# INPUTS_OUTPUTS.net
KiCad netlist of a schematic drawn in Altium Designer
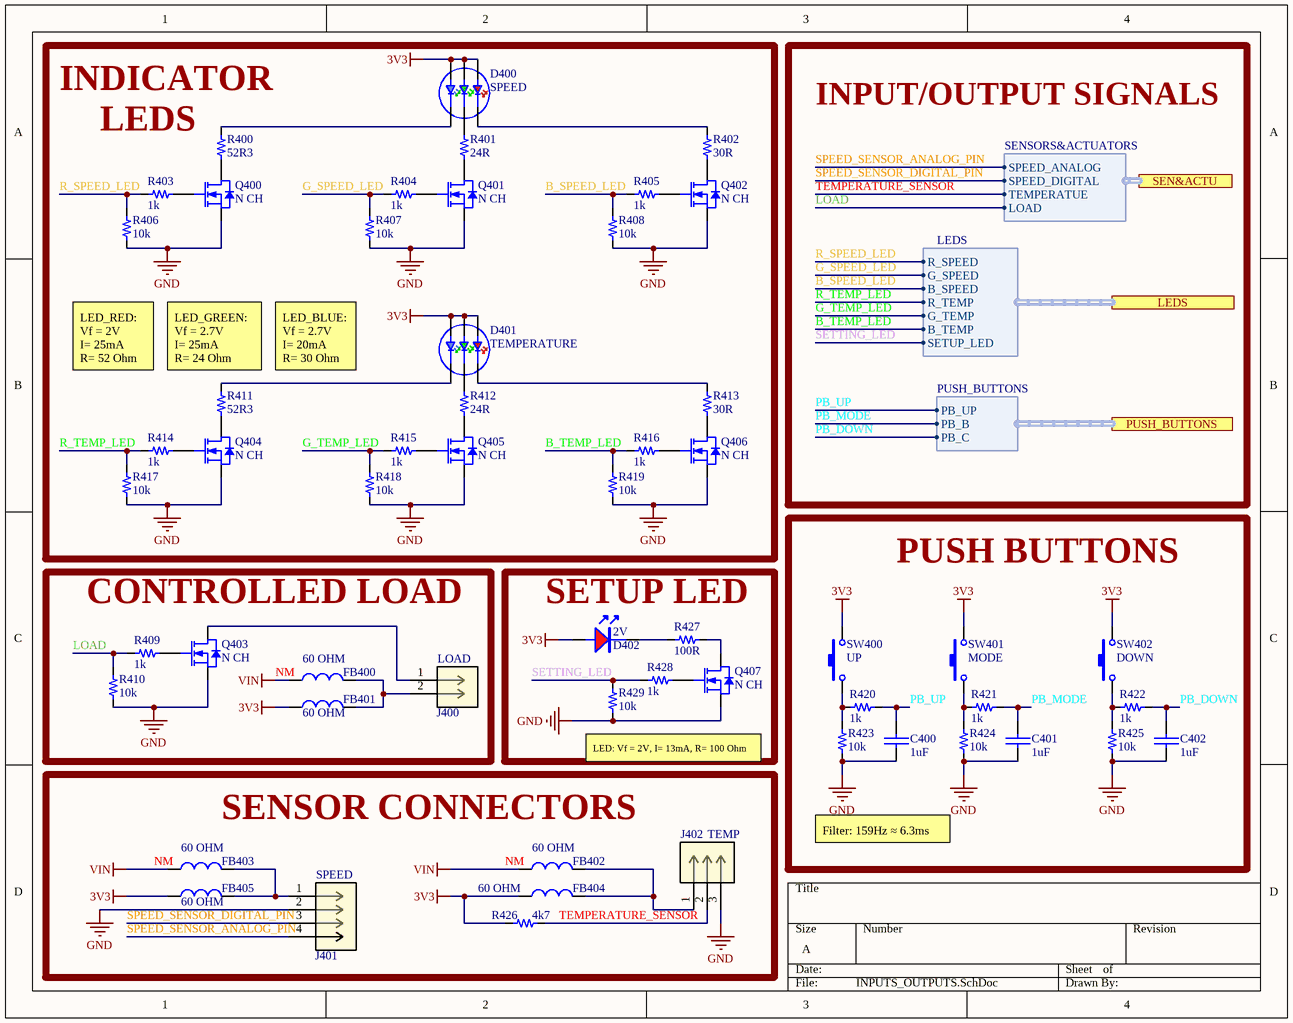
[diagram p0: INPUTS_OUTPUTS.SchDoc]

(export (version "E")
  (design (tool "Eeschema 10.0.6"))
  (components
    (comp (ref "C400")
      (value "1uF")
      (footprint "0603_cap")
      (description "50V 1uF X5R ±10% 0603 Multilayer Ceramic Capacitors MLCC - SMD/SMT ROHS")
      (fields
        (field (name "MANUFACTURER") "Samsung Electro-Mechanics")
        (field (name "MANUFACTURER PART NUMBER") "CL10A105KB8NNNC")
      )
      (libsource (lib "shared_lib") (part "Cap_1uF_0603_50V"))
    )
    (comp (ref "C401")
      (value "1uF")
      (footprint "0603_cap")
      (description "50V 1uF X5R ±10% 0603 Multilayer Ceramic Capacitors MLCC - SMD/SMT ROHS")
      (fields
        (field (name "MANUFACTURER") "Samsung Electro-Mechanics")
        (field (name "MANUFACTURER PART NUMBER") "CL10A105KB8NNNC")
      )
      (libsource (lib "shared_lib") (part "Cap_1uF_0603_50V"))
    )
    (comp (ref "C402")
      (value "1uF")
      (footprint "0603_cap")
      (description "50V 1uF X5R ±10% 0603 Multilayer Ceramic Capacitors MLCC - SMD/SMT ROHS")
      (fields
        (field (name "MANUFACTURER") "Samsung Electro-Mechanics")
        (field (name "MANUFACTURER PART NUMBER") "CL10A105KB8NNNC")
      )
      (libsource (lib "shared_lib") (part "Cap_1uF_0603_50V"))
    )
    (comp (ref "D400")
      (value "SPEED")
      (footprint "RGB_NS_3.5X3.7")
      (description "-30℃~+85℃ RGB 110° 3535(mm) Light Emitting Diodes (LED) ROHS")
      (fields
        (field (name "MANUFACTURER") "Foshan NationStar Optoelectronics")
        (field (name "MANUFACTURER PART NUMBER") "RS-3535MWAM")
      )
      (libsource (lib "shared_lib") (part "LED_RGB_3535_SMD"))
    )
    (comp (ref "D401")
      (value "TEMPERATURE")
      (footprint "RGB_NS_3.5X3.7")
      (description "-30℃~+85℃ RGB 110° 3535(mm) Light Emitting Diodes (LED) ROHS")
      (fields
        (field (name "MANUFACTURER") "Foshan NationStar Optoelectronics")
        (field (name "MANUFACTURER PART NUMBER") "RS-3535MWAM")
      )
      (libsource (lib "shared_lib") (part "LED_RGB_3535_SMD"))
    )
    (comp (ref "D402")
      (value "2V")
      (footprint "0805_LED")
      (description "LED RED CLEAR 0805 SMD")
      (fields
        (field (name "MANUFACTURER") "XINGLIGHT")
        (field (name "MANUFACTURER PART NUMBER") "XL-2012SURC")
      )
      (libsource (lib "shared_lib") (part "LED_0805_RED"))
    )
    (comp (ref "FB400")
      (value "60 OHM")
      (footprint "0603_fb")
      (description "2A 1 100mΩ 60Ω@100MHz ±25% 0603 Ferrite Beads ROHS")
      (fields
        (field (name "MANUFACTURER") "TAI-TECH")
        (field (name "MANUFACTURER PART NUMBER") "HCB1608KF-600T20")
        (field (name "USAGE") "NM")
      )
      (libsource (lib "shared_lib") (part "FB_60_0603_2A"))
    )
    (comp (ref "FB401")
      (value "60 OHM")
      (footprint "0603_fb")
      (description "2A 1 100mΩ 60Ω@100MHz ±25% 0603 Ferrite Beads ROHS")
      (fields
        (field (name "MANUFACTURER") "TAI-TECH")
        (field (name "MANUFACTURER PART NUMBER") "HCB1608KF-600T20")
      )
      (libsource (lib "shared_lib") (part "FB_60_0603_2A"))
    )
    (comp (ref "FB402")
      (value "60 OHM")
      (footprint "0603_fb")
      (description "2A 1 100mΩ 60Ω@100MHz ±25% 0603 Ferrite Beads ROHS")
      (fields
        (field (name "MANUFACTURER") "TAI-TECH")
        (field (name "MANUFACTURER PART NUMBER") "HCB1608KF-600T20")
        (field (name "USAGE") "NM")
      )
      (libsource (lib "shared_lib") (part "FB_60_0603_2A"))
    )
    (comp (ref "FB403")
      (value "60 OHM")
      (footprint "0603_fb")
      (description "2A 1 100mΩ 60Ω@100MHz ±25% 0603 Ferrite Beads ROHS")
      (fields
        (field (name "MANUFACTURER") "TAI-TECH")
        (field (name "MANUFACTURER PART NUMBER") "HCB1608KF-600T20")
        (field (name "USAGE") "NM")
      )
      (libsource (lib "shared_lib") (part "FB_60_0603_2A"))
    )
    (comp (ref "FB404")
      (value "60 OHM")
      (footprint "0603_fb")
      (description "2A 1 100mΩ 60Ω@100MHz ±25% 0603 Ferrite Beads ROHS")
      (fields
        (field (name "MANUFACTURER") "TAI-TECH")
        (field (name "MANUFACTURER PART NUMBER") "HCB1608KF-600T20")
      )
      (libsource (lib "shared_lib") (part "FB_60_0603_2A"))
    )
    (comp (ref "FB405")
      (value "60 OHM")
      (footprint "0603_fb")
      (description "2A 1 100mΩ 60Ω@100MHz ±25% 0603 Ferrite Beads ROHS")
      (fields
        (field (name "MANUFACTURER") "TAI-TECH")
        (field (name "MANUFACTURER PART NUMBER") "HCB1608KF-600T20")
      )
      (libsource (lib "shared_lib") (part "FB_60_0603_2A"))
    )
    (comp (ref "J400")
      (value "LOAD")
      (footprint "CON_2X1_TH_2.54MM")
      (description "CONN HEADER VERT 2POS 2.54MM")
      (fields
        (field (name "MANUFACTURER") "Amphenol ICC (FCI)")
        (field (name "MANUFACTURER PART NUMBER") "10129378-902001BLF")
      )
      (libsource (lib "Bicycle_project") (part "Con_2x1_TH_2.54mm"))
    )
    (comp (ref "J401")
      (value "SPEED")
      (footprint "CON_4X1_TH_2.54MM")
      (description "CONN HEADER VERT 4POS 2.54MM")
      (fields
        (field (name "MANUFACTURER") "Amphenol ICC (FCI)")
        (field (name "MANUFACTURER PART NUMBER") "10129378-904001BLF")
      )
      (libsource (lib "Bicycle_project") (part "Con_4X1_TH_2.54mm"))
    )
    (comp (ref "J402")
      (value "TEMP")
      (footprint "CON_3X1_TH_2.54MM")
      (description "CONN HEADER VERT 3POS 2.54MM")
      (fields
        (field (name "MANUFACTURER") "Amphenol ICC (FCI)")
        (field (name "MANUFACTURER PART NUMBER") "10129378-903001BLF")
      )
      (libsource (lib "Bicycle_project") (part "Con_3X1_TH_2.54mm"))
    )
    (comp (ref "Q400")
      (value "N CH")
      (footprint "SOT_23_3")
      (description "MOSFET N-CH 20V SOT23")
      (fields (field (name "MANUFACTURER") "Doeshare") (field (name "MANUFACTURER PART NUMBER") "DN2302S"))
      (libsource (lib "shared_lib") (part "Q_NFET_20V_3.2A_SOT23"))
    )
    (comp (ref "Q401")
      (value "N CH")
      (footprint "SOT_23_3")
      (description "MOSFET N-CH 20V SOT23")
      (fields (field (name "MANUFACTURER") "Doeshare") (field (name "MANUFACTURER PART NUMBER") "DN2302S"))
      (libsource (lib "shared_lib") (part "Q_NFET_20V_3.2A_SOT23"))
    )
    (comp (ref "Q402")
      (value "N CH")
      (footprint "SOT_23_3")
      (description "MOSFET N-CH 20V SOT23")
      (fields (field (name "MANUFACTURER") "Doeshare") (field (name "MANUFACTURER PART NUMBER") "DN2302S"))
      (libsource (lib "shared_lib") (part "Q_NFET_20V_3.2A_SOT23"))
    )
    (comp (ref "Q403")
      (value "N CH")
      (footprint "SOT_23_3")
      (description "MOSFET N-CH 20V SOT23")
      (fields (field (name "MANUFACTURER") "Doeshare") (field (name "MANUFACTURER PART NUMBER") "DN2302S"))
      (libsource (lib "shared_lib") (part "Q_NFET_20V_3.2A_SOT23"))
    )
    (comp (ref "Q404")
      (value "N CH")
      (footprint "SOT_23_3")
      (description "MOSFET N-CH 20V SOT23")
      (fields (field (name "MANUFACTURER") "Doeshare") (field (name "MANUFACTURER PART NUMBER") "DN2302S"))
      (libsource (lib "shared_lib") (part "Q_NFET_20V_3.2A_SOT23"))
    )
    (comp (ref "Q405")
      (value "N CH")
      (footprint "SOT_23_3")
      (description "MOSFET N-CH 20V SOT23")
      (fields (field (name "MANUFACTURER") "Doeshare") (field (name "MANUFACTURER PART NUMBER") "DN2302S"))
      (libsource (lib "shared_lib") (part "Q_NFET_20V_3.2A_SOT23"))
    )
    (comp (ref "Q406")
      (value "N CH")
      (footprint "SOT_23_3")
      (description "MOSFET N-CH 20V SOT23")
      (fields (field (name "MANUFACTURER") "Doeshare") (field (name "MANUFACTURER PART NUMBER") "DN2302S"))
      (libsource (lib "shared_lib") (part "Q_NFET_20V_3.2A_SOT23"))
    )
    (comp (ref "Q407")
      (value "N CH")
      (footprint "SOT_23_3")
      (description "MOSFET N-CH 20V SOT23")
      (fields (field (name "MANUFACTURER") "Doeshare") (field (name "MANUFACTURER PART NUMBER") "DN2302S"))
      (libsource (lib "shared_lib") (part "Q_NFET_20V_3.2A_SOT23"))
    )
    (comp (ref "R400")
      (value "52R3")
      (footprint "0603_res")
      (description "RES SMD 52R3 OHM 1% 1/10W 0603")
      (fields
        (field (name "MANUFACTURER") "FOJAN")
        (field (name "MANUFACTURER PART NUMBER") "FRC0603F52R3TS")
      )
      (libsource (lib "shared_lib") (part "Res_52R3_0603_1/10W_1"))
    )
    (comp (ref "R401")
      (value "24R")
      (footprint "0603_res")
      (description "RES SMD 24R OHM 5% 1/10W 0603")
      (fields
        (field (name "MANUFACTURER") "FOJAN")
        (field (name "MANUFACTURER PART NUMBER") "FRC0603J240 TS")
      )
      (libsource (lib "shared_lib") (part "Res_24R_0603_1/10W"))
    )
    (comp (ref "R402")
      (value "30R")
      (footprint "0603_res")
      (description "RES SMD 30R OHM 1% 1/10W 0603")
      (fields
        (field (name "MANUFACTURER") "FOJAN")
        (field (name "MANUFACTURER PART NUMBER") "FRC0603F30R0TS")
      )
      (libsource (lib "shared_lib") (part "Res_30R_0603_1/10W"))
    )
    (comp (ref "R403")
      (value "1k")
      (footprint "0603_res")
      (description "RES SMD 1k OHM 5% 1/10W 0603")
      (fields
        (field (name "MANUFACTURER") "FOJAN")
        (field (name "MANUFACTURER PART NUMBER") "FRC0603J102 TS")
      )
      (libsource (lib "shared_lib") (part "Res_1k_0603_1/10W"))
    )
    (comp (ref "R404")
      (value "1k")
      (footprint "0603_res")
      (description "RES SMD 1k OHM 5% 1/10W 0603")
      (fields
        (field (name "MANUFACTURER") "FOJAN")
        (field (name "MANUFACTURER PART NUMBER") "FRC0603J102 TS")
      )
      (libsource (lib "shared_lib") (part "Res_1k_0603_1/10W"))
    )
    (comp (ref "R405")
      (value "1k")
      (footprint "0603_res")
      (description "RES SMD 1k OHM 5% 1/10W 0603")
      (fields
        (field (name "MANUFACTURER") "FOJAN")
        (field (name "MANUFACTURER PART NUMBER") "FRC0603J102 TS")
      )
      (libsource (lib "shared_lib") (part "Res_1k_0603_1/10W"))
    )
    (comp (ref "R406")
      (value "10k")
      (footprint "0603_res")
      (description "RES SMD 10k OHM 5% 1/10W 0603")
      (fields (field (name "MANUFACTURER") "FOJAN") (field (name "MANUFACTURER PART NUMBER") "FRC0603J103TS"))
      (libsource (lib "shared_lib") (part "Res_10k_0603_1/10W"))
    )
    (comp (ref "R407")
      (value "10k")
      (footprint "0603_res")
      (description "RES SMD 10k OHM 5% 1/10W 0603")
      (fields (field (name "MANUFACTURER") "FOJAN") (field (name "MANUFACTURER PART NUMBER") "FRC0603J103TS"))
      (libsource (lib "shared_lib") (part "Res_10k_0603_1/10W"))
    )
    (comp (ref "R408")
      (value "10k")
      (footprint "0603_res")
      (description "RES SMD 10k OHM 5% 1/10W 0603")
      (fields (field (name "MANUFACTURER") "FOJAN") (field (name "MANUFACTURER PART NUMBER") "FRC0603J103TS"))
      (libsource (lib "shared_lib") (part "Res_10k_0603_1/10W"))
    )
    (comp (ref "R409")
      (value "1k")
      (footprint "0603_res")
      (description "RES SMD 1k OHM 5% 1/10W 0603")
      (fields
        (field (name "MANUFACTURER") "FOJAN")
        (field (name "MANUFACTURER PART NUMBER") "FRC0603J102 TS")
      )
      (libsource (lib "shared_lib") (part "Res_1k_0603_1/10W"))
    )
    (comp (ref "R410")
      (value "10k")
      (footprint "0603_res")
      (description "RES SMD 10k OHM 5% 1/10W 0603")
      (fields (field (name "MANUFACTURER") "FOJAN") (field (name "MANUFACTURER PART NUMBER") "FRC0603J103TS"))
      (libsource (lib "shared_lib") (part "Res_10k_0603_1/10W"))
    )
    (comp (ref "R411")
      (value "52R3")
      (footprint "0603_res")
      (description "RES SMD 52R3 OHM 1% 1/10W 0603")
      (fields
        (field (name "MANUFACTURER") "FOJAN")
        (field (name "MANUFACTURER PART NUMBER") "FRC0603F52R3TS")
      )
      (libsource (lib "shared_lib") (part "Res_52R3_0603_1/10W_1"))
    )
    (comp (ref "R412")
      (value "24R")
      (footprint "0603_res")
      (description "RES SMD 24R OHM 5% 1/10W 0603")
      (fields
        (field (name "MANUFACTURER") "FOJAN")
        (field (name "MANUFACTURER PART NUMBER") "FRC0603J240 TS")
      )
      (libsource (lib "shared_lib") (part "Res_24R_0603_1/10W"))
    )
    (comp (ref "R413")
      (value "30R")
      (footprint "0603_res")
      (description "RES SMD 30R OHM 1% 1/10W 0603")
      (fields
        (field (name "MANUFACTURER") "FOJAN")
        (field (name "MANUFACTURER PART NUMBER") "FRC0603F30R0TS")
      )
      (libsource (lib "shared_lib") (part "Res_30R_0603_1/10W"))
    )
    (comp (ref "R414")
      (value "1k")
      (footprint "0603_res")
      (description "RES SMD 1k OHM 5% 1/10W 0603")
      (fields
        (field (name "MANUFACTURER") "FOJAN")
        (field (name "MANUFACTURER PART NUMBER") "FRC0603J102 TS")
      )
      (libsource (lib "shared_lib") (part "Res_1k_0603_1/10W"))
    )
    (comp (ref "R415")
      (value "1k")
      (footprint "0603_res")
      (description "RES SMD 1k OHM 5% 1/10W 0603")
      (fields
        (field (name "MANUFACTURER") "FOJAN")
        (field (name "MANUFACTURER PART NUMBER") "FRC0603J102 TS")
      )
      (libsource (lib "shared_lib") (part "Res_1k_0603_1/10W"))
    )
    (comp (ref "R416")
      (value "1k")
      (footprint "0603_res")
      (description "RES SMD 1k OHM 5% 1/10W 0603")
      (fields
        (field (name "MANUFACTURER") "FOJAN")
        (field (name "MANUFACTURER PART NUMBER") "FRC0603J102 TS")
      )
      (libsource (lib "shared_lib") (part "Res_1k_0603_1/10W"))
    )
    (comp (ref "R417")
      (value "10k")
      (footprint "0603_res")
      (description "RES SMD 10k OHM 5% 1/10W 0603")
      (fields (field (name "MANUFACTURER") "FOJAN") (field (name "MANUFACTURER PART NUMBER") "FRC0603J103TS"))
      (libsource (lib "shared_lib") (part "Res_10k_0603_1/10W"))
    )
    (comp (ref "R418")
      (value "10k")
      (footprint "0603_res")
      (description "RES SMD 10k OHM 5% 1/10W 0603")
      (fields (field (name "MANUFACTURER") "FOJAN") (field (name "MANUFACTURER PART NUMBER") "FRC0603J103TS"))
      (libsource (lib "shared_lib") (part "Res_10k_0603_1/10W"))
    )
    (comp (ref "R419")
      (value "10k")
      (footprint "0603_res")
      (description "RES SMD 10k OHM 5% 1/10W 0603")
      (fields (field (name "MANUFACTURER") "FOJAN") (field (name "MANUFACTURER PART NUMBER") "FRC0603J103TS"))
      (libsource (lib "shared_lib") (part "Res_10k_0603_1/10W"))
    )
    (comp (ref "R420")
      (value "1k")
      (footprint "0603_res")
      (description "RES SMD 1k OHM 5% 1/10W 0603")
      (fields
        (field (name "MANUFACTURER") "FOJAN")
        (field (name "MANUFACTURER PART NUMBER") "FRC0603J102 TS")
      )
      (libsource (lib "shared_lib") (part "Res_1k_0603_1/10W"))
    )
    (comp (ref "R421")
      (value "1k")
      (footprint "0603_res")
      (description "RES SMD 1k OHM 5% 1/10W 0603")
      (fields
        (field (name "MANUFACTURER") "FOJAN")
        (field (name "MANUFACTURER PART NUMBER") "FRC0603J102 TS")
      )
      (libsource (lib "shared_lib") (part "Res_1k_0603_1/10W"))
    )
    (comp (ref "R422")
      (value "1k")
      (footprint "0603_res")
      (description "RES SMD 1k OHM 5% 1/10W 0603")
      (fields
        (field (name "MANUFACTURER") "FOJAN")
        (field (name "MANUFACTURER PART NUMBER") "FRC0603J102 TS")
      )
      (libsource (lib "shared_lib") (part "Res_1k_0603_1/10W"))
    )
    (comp (ref "R423")
      (value "10k")
      (footprint "0603_res")
      (description "RES SMD 10k OHM 5% 1/10W 0603")
      (fields (field (name "MANUFACTURER") "FOJAN") (field (name "MANUFACTURER PART NUMBER") "FRC0603J103TS"))
      (libsource (lib "shared_lib") (part "Res_10k_0603_1/10W"))
    )
    (comp (ref "R424")
      (value "10k")
      (footprint "0603_res")
      (description "RES SMD 10k OHM 5% 1/10W 0603")
      (fields (field (name "MANUFACTURER") "FOJAN") (field (name "MANUFACTURER PART NUMBER") "FRC0603J103TS"))
      (libsource (lib "shared_lib") (part "Res_10k_0603_1/10W"))
    )
    (comp (ref "R425")
      (value "10k")
      (footprint "0603_res")
      (description "RES SMD 10k OHM 5% 1/10W 0603")
      (fields (field (name "MANUFACTURER") "FOJAN") (field (name "MANUFACTURER PART NUMBER") "FRC0603J103TS"))
      (libsource (lib "shared_lib") (part "Res_10k_0603_1/10W"))
    )
    (comp (ref "R426")
      (value "4k7")
      (footprint "0603_res")
      (description "RES SMD 4k7 OHM 5% 1/10W 0603")
      (fields
        (field (name "MANUFACTURER") "FOJAN")
        (field (name "MANUFACTURER PART NUMBER") "FRC0603J472 TS")
      )
      (libsource (lib "shared_lib") (part "Res_4k7_0603_1/10W"))
    )
    (comp (ref "R427")
      (value "100R")
      (footprint "0603_res")
      (description "RES SMD 100R OHM 5% 1/10W 0603")
      (fields
        (field (name "MANUFACTURER") "FOJAN")
        (field (name "MANUFACTURER PART NUMBER") "FRC0603J101 TS")
      )
      (libsource (lib "shared_lib") (part "Res_100R_0603_1/10W"))
    )
    (comp (ref "R428")
      (value "1k")
      (footprint "0603_res")
      (description "RES SMD 1k OHM 5% 1/10W 0603")
      (fields
        (field (name "MANUFACTURER") "FOJAN")
        (field (name "MANUFACTURER PART NUMBER") "FRC0603J102 TS")
      )
      (libsource (lib "shared_lib") (part "Res_1k_0603_1/10W"))
    )
    (comp (ref "R429")
      (value "10k")
      (footprint "0603_res")
      (description "RES SMD 10k OHM 5% 1/10W 0603")
      (fields (field (name "MANUFACTURER") "FOJAN") (field (name "MANUFACTURER PART NUMBER") "FRC0603J103TS"))
      (libsource (lib "shared_lib") (part "Res_10k_0603_1/10W"))
    )
    (comp (ref "SW400")
      (value "UP")
      (footprint "Sw_PUSH_4.5x4.5x5mm")
      (description "SWITCH TACTILE SPST-NO 0.05A 12V")
      (fields
        (field (name "MANUFACTURER") "BZCN")
        (field (name "MANUFACTURER PART NUMBER") "TSC015A05026A")
        (field (name "LAST MODIFIED BY") "N-A.Potosi")
      )
      (libsource (lib "shared_lib") (part "Sw_PUSH_4.5x4.5x5.0xmm"))
    )
    (comp (ref "SW401")
      (value "MODE")
      (footprint "Sw_PUSH_4.5x4.5x5mm")
      (description "SWITCH TACTILE SPST-NO 0.05A 12V")
      (fields
        (field (name "MANUFACTURER") "BZCN")
        (field (name "MANUFACTURER PART NUMBER") "TSC015A05026A")
        (field (name "LAST MODIFIED BY") "N-A.Potosi")
      )
      (libsource (lib "shared_lib") (part "Sw_PUSH_4.5x4.5x5.0xmm"))
    )
    (comp (ref "SW402")
      (value "DOWN")
      (footprint "Sw_PUSH_4.5x4.5x5mm")
      (description "SWITCH TACTILE SPST-NO 0.05A 12V")
      (fields
        (field (name "MANUFACTURER") "BZCN")
        (field (name "MANUFACTURER PART NUMBER") "TSC015A05026A")
        (field (name "LAST MODIFIED BY") "N-A.Potosi")
      )
      (libsource (lib "shared_lib") (part "Sw_PUSH_4.5x4.5x5.0xmm"))
    )
  )
  (nets
    (net (code "4") (name "/B_SPEED_LED") (class "Default")
      (node (ref "R405") (pin "1") (pinfunction "1_1") (pintype "passive"))
      (node (ref "R408") (pin "2") (pinfunction "2_2") (pintype "passive"))
    )
    (net (code "5") (name "/B_TEMP_LED") (class "Default")
      (node (ref "R416") (pin "1") (pinfunction "1_1") (pintype "passive"))
      (node (ref "R419") (pin "2") (pinfunction "2_2") (pintype "passive"))
    )
    (net (code "6") (name "/G_SPEED_LED") (class "Default")
      (node (ref "R404") (pin "1") (pinfunction "1_1") (pintype "passive"))
      (node (ref "R407") (pin "2") (pinfunction "2_2") (pintype "passive"))
    )
    (net (code "7") (name "/G_TEMP_LED") (class "Default")
      (node (ref "R415") (pin "1") (pinfunction "1_1") (pintype "passive"))
      (node (ref "R418") (pin "2") (pinfunction "2_2") (pintype "passive"))
    )
    (net (code "8") (name "/LOAD") (class "Default")
      (node (ref "R409") (pin "1") (pinfunction "1_1") (pintype "passive"))
      (node (ref "R410") (pin "2") (pinfunction "2_2") (pintype "passive"))
    )
    (net (code "9") (name "/PB_DOWN") (class "Default")
      (node (ref "C402") (pin "2") (pinfunction "2_2") (pintype "passive"))
      (node (ref "R422") (pin "2") (pinfunction "2_2") (pintype "passive"))
    )
    (net (code "10") (name "/PB_MODE") (class "Default")
      (node (ref "C401") (pin "2") (pinfunction "2_2") (pintype "passive"))
      (node (ref "R421") (pin "2") (pinfunction "2_2") (pintype "passive"))
    )
    (net (code "11") (name "/PB_UP") (class "Default")
      (node (ref "C400") (pin "2") (pinfunction "2_2") (pintype "passive"))
      (node (ref "R420") (pin "2") (pinfunction "2_2") (pintype "passive"))
    )
    (net (code "12") (name "/R_SPEED_LED") (class "Default")
      (node (ref "R403") (pin "1") (pinfunction "1_1") (pintype "passive"))
      (node (ref "R406") (pin "2") (pinfunction "2_2") (pintype "passive"))
    )
    (net (code "13") (name "/R_TEMP_LED") (class "Default")
      (node (ref "R414") (pin "1") (pinfunction "1_1") (pintype "passive"))
      (node (ref "R417") (pin "2") (pinfunction "2_2") (pintype "passive"))
    )
    (net (code "14") (name "/SETTING_LED") (class "Default")
      (node (ref "R428") (pin "1") (pinfunction "1_1") (pintype "passive"))
      (node (ref "R429") (pin "2") (pinfunction "2_2") (pintype "passive"))
    )
    (net (code "15") (name "/SPEED_SENSOR_ANALOG_PIN") (class "Default")
      (node (ref "J401") (pin "4") (pinfunction "4_4") (pintype "passive"))
    )
    (net (code "16") (name "/SPEED_SENSOR_DIGITAL_PIN") (class "Default")
      (node (ref "J401") (pin "3") (pinfunction "3_3") (pintype "passive"))
    )
    (net (code "17") (name "/TEMPERATURE_SENSOR") (class "Default")
      (node (ref "J402") (pin "2") (pinfunction "2_2") (pintype "passive"))
      (node (ref "R426") (pin "2") (pinfunction "2_2") (pintype "passive"))
    )
    (net (code "21") (name "3V3") (class "Default")
      (node (ref "D400") (pin "4") (pinfunction "4_4") (pintype "passive"))
      (node (ref "D400") (pin "5") (pinfunction "5_5") (pintype "passive"))
      (node (ref "D400") (pin "6") (pinfunction "6_6") (pintype "passive"))
      (node (ref "D401") (pin "4") (pinfunction "4_4") (pintype "passive"))
      (node (ref "D401") (pin "5") (pinfunction "5_5") (pintype "passive"))
      (node (ref "D401") (pin "6") (pinfunction "6_6") (pintype "passive"))
      (node (ref "D402") (pin "1") (pinfunction "A_1") (pintype "passive"))
      (node (ref "FB401") (pin "1") (pinfunction "1_1") (pintype "passive"))
      (node (ref "FB404") (pin "1") (pinfunction "1_1") (pintype "passive"))
      (node (ref "FB405") (pin "1") (pinfunction "1_1") (pintype "passive"))
      (node (ref "R426") (pin "1") (pinfunction "1_1") (pintype "passive"))
      (node (ref "SW400") (pin "2") (pinfunction "2_2") (pintype "passive"))
      (node (ref "SW401") (pin "2") (pinfunction "2_2") (pintype "passive"))
      (node (ref "SW402") (pin "2") (pinfunction "2_2") (pintype "passive"))
    )
    (net (code "22") (name "GND") (class "Default")
      (node (ref "C400") (pin "1") (pinfunction "1_1") (pintype "passive"))
      (node (ref "C401") (pin "1") (pinfunction "1_1") (pintype "passive"))
      (node (ref "C402") (pin "1") (pinfunction "1_1") (pintype "passive"))
      (node (ref "J401") (pin "2") (pinfunction "2_2") (pintype "passive"))
      (node (ref "J402") (pin "3") (pinfunction "3_3") (pintype "passive"))
      (node (ref "Q400") (pin "2") (pinfunction "S_2") (pintype "passive"))
      (node (ref "Q401") (pin "2") (pinfunction "S_2") (pintype "passive"))
      (node (ref "Q402") (pin "2") (pinfunction "S_2") (pintype "passive"))
      (node (ref "Q403") (pin "2") (pinfunction "S_2") (pintype "passive"))
      (node (ref "Q404") (pin "2") (pinfunction "S_2") (pintype "passive"))
      (node (ref "Q405") (pin "2") (pinfunction "S_2") (pintype "passive"))
      (node (ref "Q406") (pin "2") (pinfunction "S_2") (pintype "passive"))
      (node (ref "Q407") (pin "2") (pinfunction "S_2") (pintype "passive"))
      (node (ref "R406") (pin "1") (pinfunction "1_1") (pintype "passive"))
      (node (ref "R407") (pin "1") (pinfunction "1_1") (pintype "passive"))
      (node (ref "R408") (pin "1") (pinfunction "1_1") (pintype "passive"))
      (node (ref "R410") (pin "1") (pinfunction "1_1") (pintype "passive"))
      (node (ref "R417") (pin "1") (pinfunction "1_1") (pintype "passive"))
      (node (ref "R418") (pin "1") (pinfunction "1_1") (pintype "passive"))
      (node (ref "R419") (pin "1") (pinfunction "1_1") (pintype "passive"))
      (node (ref "R423") (pin "1") (pinfunction "1_1") (pintype "passive"))
      (node (ref "R424") (pin "1") (pinfunction "1_1") (pintype "passive"))
      (node (ref "R425") (pin "1") (pinfunction "1_1") (pintype "passive"))
      (node (ref "R429") (pin "1") (pinfunction "1_1") (pintype "passive"))
    )
    (net (code "23") (name "Net-(D400-Pad1)") (class "Default")
      (node (ref "D400") (pin "1") (pinfunction "1_1") (pintype "passive"))
      (node (ref "R400") (pin "2") (pinfunction "2_2") (pintype "passive"))
    )
    (net (code "24") (name "Net-(D400-Pad2)") (class "Default")
      (node (ref "D400") (pin "2") (pinfunction "2_2") (pintype "passive"))
      (node (ref "R401") (pin "2") (pinfunction "2_2") (pintype "passive"))
    )
    (net (code "25") (name "Net-(D400-Pad3)") (class "Default")
      (node (ref "D400") (pin "3") (pinfunction "3_3") (pintype "passive"))
      (node (ref "R402") (pin "2") (pinfunction "2_2") (pintype "passive"))
    )
    (net (code "26") (name "Net-(D401-Pad1)") (class "Default")
      (node (ref "D401") (pin "1") (pinfunction "1_1") (pintype "passive"))
      (node (ref "R411") (pin "2") (pinfunction "2_2") (pintype "passive"))
    )
    (net (code "27") (name "Net-(D401-Pad2)") (class "Default")
      (node (ref "D401") (pin "2") (pinfunction "2_2") (pintype "passive"))
      (node (ref "R412") (pin "2") (pinfunction "2_2") (pintype "passive"))
    )
    (net (code "28") (name "Net-(D401-Pad3)") (class "Default")
      (node (ref "D401") (pin "3") (pinfunction "3_3") (pintype "passive"))
      (node (ref "R413") (pin "2") (pinfunction "2_2") (pintype "passive"))
    )
    (net (code "29") (name "Net-(D402-Pad2)") (class "Default")
      (node (ref "D402") (pin "2") (pinfunction "2_2") (pintype "passive"))
      (node (ref "R427") (pin "2") (pinfunction "2_2") (pintype "passive"))
    )
    (net (code "30") (name "Net-(FB400-Pad2)") (class "Default")
      (node (ref "FB400") (pin "2") (pinfunction "2_2") (pintype "passive"))
      (node (ref "FB401") (pin "2") (pinfunction "2_2") (pintype "passive"))
      (node (ref "J400") (pin "2") (pinfunction "2_2") (pintype "passive"))
    )
    (net (code "31") (name "Net-(FB402-Pad2)") (class "Default")
      (node (ref "FB402") (pin "2") (pinfunction "2_2") (pintype "passive"))
      (node (ref "FB404") (pin "2") (pinfunction "2_2") (pintype "passive"))
      (node (ref "J402") (pin "1") (pinfunction "1_1") (pintype "passive"))
    )
    (net (code "32") (name "Net-(FB403-Pad2)") (class "Default")
      (node (ref "FB403") (pin "2") (pinfunction "2_2") (pintype "passive"))
      (node (ref "FB405") (pin "2") (pinfunction "2_2") (pintype "passive"))
      (node (ref "J401") (pin "1") (pinfunction "1_1") (pintype "passive"))
    )
    (net (code "33") (name "Net-(Q400-D)") (class "Default")
      (node (ref "Q400") (pin "3") (pinfunction "D_3") (pintype "passive"))
      (node (ref "R400") (pin "1") (pinfunction "1_1") (pintype "passive"))
    )
    (net (code "34") (name "Net-(Q400-G)") (class "Default")
      (node (ref "Q400") (pin "1") (pinfunction "G_1") (pintype "passive"))
      (node (ref "R403") (pin "2") (pinfunction "2_2") (pintype "passive"))
    )
    (net (code "35") (name "Net-(Q401-D)") (class "Default")
      (node (ref "Q401") (pin "3") (pinfunction "D_3") (pintype "passive"))
      (node (ref "R401") (pin "1") (pinfunction "1_1") (pintype "passive"))
    )
    (net (code "36") (name "Net-(Q401-G)") (class "Default")
      (node (ref "Q401") (pin "1") (pinfunction "G_1") (pintype "passive"))
      (node (ref "R404") (pin "2") (pinfunction "2_2") (pintype "passive"))
    )
    (net (code "37") (name "Net-(Q402-D)") (class "Default")
      (node (ref "Q402") (pin "3") (pinfunction "D_3") (pintype "passive"))
      (node (ref "R402") (pin "1") (pinfunction "1_1") (pintype "passive"))
    )
    (net (code "38") (name "Net-(Q402-G)") (class "Default")
      (node (ref "Q402") (pin "1") (pinfunction "G_1") (pintype "passive"))
      (node (ref "R405") (pin "2") (pinfunction "2_2") (pintype "passive"))
    )
    (net (code "39") (name "Net-(Q403-D)") (class "Default")
      (node (ref "J400") (pin "1") (pinfunction "1_1") (pintype "passive"))
      (node (ref "Q403") (pin "3") (pinfunction "D_3") (pintype "passive"))
    )
    (net (code "40") (name "Net-(Q403-G)") (class "Default")
      (node (ref "Q403") (pin "1") (pinfunction "G_1") (pintype "passive"))
      (node (ref "R409") (pin "2") (pinfunction "2_2") (pintype "passive"))
    )
    (net (code "41") (name "Net-(Q404-D)") (class "Default")
      (node (ref "Q404") (pin "3") (pinfunction "D_3") (pintype "passive"))
      (node (ref "R411") (pin "1") (pinfunction "1_1") (pintype "passive"))
    )
    (net (code "42") (name "Net-(Q404-G)") (class "Default")
      (node (ref "Q404") (pin "1") (pinfunction "G_1") (pintype "passive"))
      (node (ref "R414") (pin "2") (pinfunction "2_2") (pintype "passive"))
    )
    (net (code "43") (name "Net-(Q405-D)") (class "Default")
      (node (ref "Q405") (pin "3") (pinfunction "D_3") (pintype "passive"))
      (node (ref "R412") (pin "1") (pinfunction "1_1") (pintype "passive"))
    )
    (net (code "44") (name "Net-(Q405-G)") (class "Default")
      (node (ref "Q405") (pin "1") (pinfunction "G_1") (pintype "passive"))
      (node (ref "R415") (pin "2") (pinfunction "2_2") (pintype "passive"))
    )
    (net (code "45") (name "Net-(Q406-D)") (class "Default")
      (node (ref "Q406") (pin "3") (pinfunction "D_3") (pintype "passive"))
      (node (ref "R413") (pin "1") (pinfunction "1_1") (pintype "passive"))
    )
    (net (code "46") (name "Net-(Q406-G)") (class "Default")
      (node (ref "Q406") (pin "1") (pinfunction "G_1") (pintype "passive"))
      (node (ref "R416") (pin "2") (pinfunction "2_2") (pintype "passive"))
    )
    (net (code "47") (name "Net-(Q407-D)") (class "Default")
      (node (ref "Q407") (pin "3") (pinfunction "D_3") (pintype "passive"))
      (node (ref "R427") (pin "1") (pinfunction "1_1") (pintype "passive"))
    )
    (net (code "48") (name "Net-(Q407-G)") (class "Default")
      (node (ref "Q407") (pin "1") (pinfunction "G_1") (pintype "passive"))
      (node (ref "R428") (pin "2") (pinfunction "2_2") (pintype "passive"))
    )
    (net (code "49") (name "Net-(R420-Pad1)") (class "Default")
      (node (ref "R420") (pin "1") (pinfunction "1_1") (pintype "passive"))
      (node (ref "R423") (pin "2") (pinfunction "2_2") (pintype "passive"))
      (node (ref "SW400") (pin "1") (pinfunction "1_1") (pintype "passive"))
    )
    (net (code "50") (name "Net-(R421-Pad1)") (class "Default")
      (node (ref "R421") (pin "1") (pinfunction "1_1") (pintype "passive"))
      (node (ref "R424") (pin "2") (pinfunction "2_2") (pintype "passive"))
      (node (ref "SW401") (pin "1") (pinfunction "1_1") (pintype "passive"))
    )
    (net (code "51") (name "Net-(R422-Pad1)") (class "Default")
      (node (ref "R422") (pin "1") (pinfunction "1_1") (pintype "passive"))
      (node (ref "R425") (pin "2") (pinfunction "2_2") (pintype "passive"))
      (node (ref "SW402") (pin "1") (pinfunction "1_1") (pintype "passive"))
    )
    (net (code "52") (name "VIN") (class "Default")
      (node (ref "FB400") (pin "1") (pinfunction "1_1") (pintype "passive"))
      (node (ref "FB402") (pin "1") (pinfunction "1_1") (pintype "passive"))
      (node (ref "FB403") (pin "1") (pinfunction "1_1") (pintype "passive"))
    )
  )
)
